# Carte_E3e_Projet_CAERUS_etudiant_ABD.net
KiCad netlist of a schematic drawn in Altium Designer
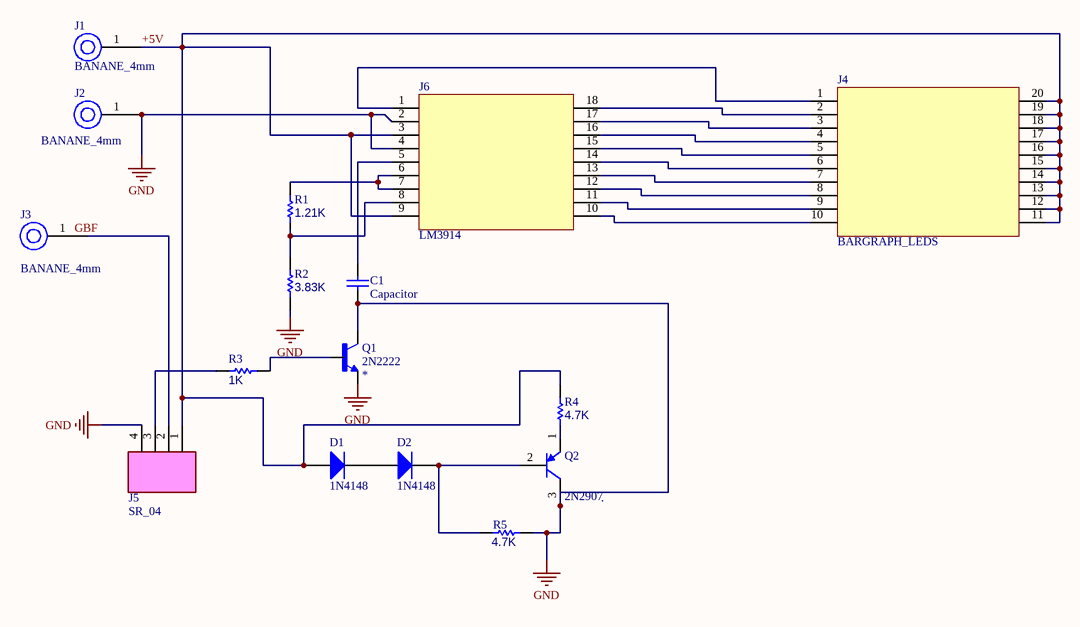
[diagram p0: Carte E3e Projet CAERUS etudiant ABD.SchDoc]

(export (version "E")
  (design (tool "Eeschema 10.0.6"))
  (components
    (comp (ref "C1")
      (value "Condensateur")
      (footprint "C0805_N")
      (description "Capacitor")
      (fields
        (field (name "TYPE") "Capacitor")
        (field (name "SOURCE") "robot_eseo.SchLib")
        (field (name "PUBLISHER") "Altium Limited")
      )
      (libsource (lib "ESEO (Ecole Supérieure d'Electronique de l'Ouest)") (part "Condensateur"))
    )
    (comp (ref "D1")
      (value "1N4148")
      (footprint "NXP-SOD27-2_V")
      (description "High Speed Diode, 100 V, 0.45 A, -65 to 175 degC, 2-Pin SOD27, RoHS, Bulk")
      (fields (field (name "POWER") "500mW") (field (name "MANUFACTURER") "Fairchild"))
      (libsource (lib "ESEO (Ecole Supérieure d'Electronique de l'Ouest)") (part "D-AK-2"))
    )
    (comp (ref "D2")
      (value "1N4148")
      (footprint "NXP-SOD27-2_V")
      (description "High Speed Diode, 100 V, 0.45 A, -65 to 175 degC, 2-Pin SOD27, RoHS, Bulk")
      (fields (field (name "POWER") "500mW") (field (name "MANUFACTURER") "Fairchild"))
      (libsource (lib "ESEO (Ecole Supérieure d'Electronique de l'Ouest)") (part "D-AK-2"))
    )
    (comp (ref "J1")
      (value "DOUILLE BANANE 4mm")
      (footprint "DOUILLE_BANANE_4mm")
      (description "DOUILLE BANANE 4 mm")
      (fields (field (name "TYPE") "BANANE_4mm"))
      (libsource (lib "connecteurs") (part "DOUILLE_BANANE_4mm"))
    )
    (comp (ref "J2")
      (value "DOUILLE BANANE 4mm")
      (footprint "DOUILLE_BANANE_4mm")
      (description "DOUILLE BANANE 4 mm")
      (fields (field (name "TYPE") "BANANE_4mm"))
      (libsource (lib "connecteurs") (part "DOUILLE_BANANE_4mm"))
    )
    (comp (ref "J3")
      (value "~")
      (footprint "DOUILLE_BANANE_4mm")
      (description "DOUILLE BANANE 4 mm")
      (fields (field (name "TYPE") "BANANE_4mm") (field (name "SOURCE") "connecteurs.SchLib"))
      (libsource (lib "ESEO (Ecole Supérieure d'Electronique de l'Ouest)") (part "DOUILLE_BANANE_4mm"))
    )
    (comp (ref "J4")
      (value "COMPOSANT_20_BROCHES")
      (footprint "DIP20_PAS=2.54_LARG=7.62_LONG=25.6")
      (fields (field (name "TYPE") "BARGRAPH_LEDS"))
      (libsource (lib "circuits integres") (part "SYMBOLE_COMPOSANT_20_BROCHES"))
    )
    (comp (ref "J5")
      (value "BARRETTE_4 CONTACTS_1 RANGEE_FEMELLE_DROITE")
      (footprint "BARRETTE_4_F_D")
      (description "BARRETTE 4 CONTACTS 1 RANGEE FEMELLE DROITE")
      (fields (field (name "TYPE") "SR_04"))
      (libsource (lib "connecteurs") (part "BARRETTE_4 CONTACTS_1 RANGEE_FEMELLE_DROITE"))
    )
    (comp (ref "J6")
      (value "COMPOSANT_18_BROCHES")
      (footprint "DIP18_PAS=2.54_LARG=7.62_LONG=23")
      (fields (field (name "TYPE") "LM3914"))
      (libsource (lib "circuits integres") (part "SYMBOLE_COMPOSANT_18_BROCHES"))
    )
    (comp (ref "Q1")
      (value "2N2222")
      (footprint "TO127P584H533-3")
      (description "Bipolar (BJT) Transistor NPN 50V 800mA 300mW Surface Mount Ceramic SMD")
      (fields (field (name "MF") "ON Semiconductor") (field (name "ALTIUM_VALUE") "*"))
      (libsource (lib "ESEO (Ecole Supérieure d'Electronique de l'Ouest)") (part "2N2222"))
    )
    (comp (ref "Q2")
      (value ".")
      (footprint "TRANSISTOR_BIPOL_TO18_EBC")
      (description "TRANSISTOR PNP TO18_EBC : 2N2907")
      (fields (field (name "TYPE") "2N2907") (field (name "SOURCE") "composants actifs.SchLib"))
      (libsource (lib "ESEO (Ecole Supérieure d'Electronique de l'Ouest)") (part "TRANSISTOR_PNP_TO92_EBC {colon} 2N5401"))
    )
    (comp (ref "R1")
      (value "1.21K")
      (footprint "RESISTANCE_1/2W")
      (description "RESISTANCE TRAVERSANTE AXIALE 1/4W")
      (fields (field (name "Comment") "RESISTANCE_AXIALE_1/4W"))
      (libsource (lib "composants passifs") (part "RESISTANCE_AXIALE_1/4W"))
    )
    (comp (ref "R2")
      (value "3.83K")
      (footprint "RESISTANCE_1/2W")
      (description "RESISTANCE TRAVERSANTE AXIALE 1/4W")
      (fields (field (name "Comment") "RESISTANCE_AXIALE_1/4W"))
      (libsource (lib "composants passifs") (part "RESISTANCE_AXIALE_1/4W"))
    )
    (comp (ref "R3")
      (value "1K")
      (footprint "RESISTANCE_1/2W")
      (description "RESISTANCE TRAVERSANTE AXIALE 1/4W")
      (fields (field (name "Comment") "RESISTANCE_AXIALE_1/4W"))
      (libsource (lib "composants passifs") (part "RESISTANCE_AXIALE_1/4W"))
    )
    (comp (ref "R4")
      (value "4.7K")
      (footprint "RESISTANCE_1W")
      (description "RESISTANCE TRAVERSANTE AXIALE 1W")
      (fields
        (field (name "Comment") "RESISTANCE_AXIALE_1W")
        (field (name "SOURCE") "composants passifs.SchLib")
      )
      (libsource (lib "ESEO (Ecole Supérieure d'Electronique de l'Ouest)") (part "RESISTANCE_AXIALE_1/4W"))
    )
    (comp (ref "R5")
      (value "4.7K")
      (footprint "RESISTANCE_1W")
      (description "RESISTANCE TRAVERSANTE AXIALE 1W")
      (fields
        (field (name "Comment") "RESISTANCE_AXIALE_1W")
        (field (name "SOURCE") "composants passifs.SchLib")
      )
      (libsource (lib "ESEO (Ecole Supérieure d'Electronique de l'Ouest)") (part "RESISTANCE_AXIALE_1/4W"))
    )
  )
  (nets
    (net (code "1") (name "/+5V") (class "Default")
      (node (ref "D1") (pin "1") (pinfunction "A_1") (pintype "passive"))
      (node (ref "J1") (pin "1") (pinfunction "1_1") (pintype "passive"))
      (node (ref "J4") (pin "11") (pintype "passive"))
      (node (ref "J4") (pin "12") (pintype "passive"))
      (node (ref "J4") (pin "13") (pintype "passive"))
      (node (ref "J4") (pin "14") (pintype "passive"))
      (node (ref "J4") (pin "15") (pintype "passive"))
      (node (ref "J4") (pin "16") (pintype "passive"))
      (node (ref "J4") (pin "17") (pintype "passive"))
      (node (ref "J4") (pin "18") (pintype "passive"))
      (node (ref "J4") (pin "19") (pintype "passive"))
      (node (ref "J4") (pin "20") (pintype "passive"))
      (node (ref "J5") (pin "1") (pinfunction "1_1") (pintype "passive"))
      (node (ref "J6") (pin "3") (pintype "passive"))
      (node (ref "J6") (pin "9") (pintype "passive"))
      (node (ref "R4") (pin "2") (pinfunction "2_2") (pintype "passive"))
    )
    (net (code "2") (name "GND") (class "Default")
      (node (ref "C1") (pin "1") (pinfunction "1_1") (pintype "passive"))
      (node (ref "J2") (pin "1") (pinfunction "1_1") (pintype "passive"))
      (node (ref "J5") (pin "4") (pinfunction "4_4") (pintype "passive"))
      (node (ref "J6") (pin "2") (pintype "passive"))
      (node (ref "J6") (pin "4") (pintype "passive"))
      (node (ref "Q1") (pin "1") (pinfunction "E_1") (pintype "passive"))
      (node (ref "Q1") (pin "3") (pinfunction "C_3") (pintype "passive"))
      (node (ref "Q2") (pin "3") (pinfunction "C_3") (pintype "passive"))
      (node (ref "R2") (pin "1") (pinfunction "1_1") (pintype "passive"))
      (node (ref "R5") (pin "2") (pinfunction "2_2") (pintype "passive"))
    )
    (net (code "3") (name "Net-(C1-Pad2)") (class "Default")
      (node (ref "C1") (pin "2") (pinfunction "2_2") (pintype "passive"))
      (node (ref "J6") (pin "5") (pintype "passive"))
    )
    (net (code "4") (name "Net-(D1-K)") (class "Default")
      (node (ref "D1") (pin "2") (pinfunction "K_2") (pintype "passive"))
      (node (ref "D2") (pin "1") (pinfunction "A_1") (pintype "passive"))
    )
    (net (code "5") (name "Net-(D2-K)") (class "Default")
      (node (ref "D2") (pin "2") (pinfunction "K_2") (pintype "passive"))
      (node (ref "Q2") (pin "2") (pinfunction "B_2") (pintype "passive"))
      (node (ref "R5") (pin "1") (pinfunction "1_1") (pintype "passive"))
    )
    (net (code "6") (name "Net-(J3-Pad1)") (class "Default")
      (node (ref "J3") (pin "1") (pinfunction "1_1") (pintype "passive"))
      (node (ref "J5") (pin "2") (pinfunction "2_2") (pintype "passive"))
    )
    (net (code "7") (name "Net-(J4-Pad1)") (class "Default")
      (node (ref "J4") (pin "1") (pintype "passive"))
      (node (ref "J6") (pin "1") (pintype "passive"))
    )
    (net (code "8") (name "Net-(J4-Pad2)") (class "Default")
      (node (ref "J4") (pin "2") (pintype "passive"))
      (node (ref "J6") (pin "18") (pintype "passive"))
    )
    (net (code "9") (name "Net-(J4-Pad3)") (class "Default")
      (node (ref "J4") (pin "3") (pintype "passive"))
      (node (ref "J6") (pin "17") (pintype "passive"))
    )
    (net (code "10") (name "Net-(J4-Pad4)") (class "Default")
      (node (ref "J4") (pin "4") (pintype "passive"))
      (node (ref "J6") (pin "16") (pintype "passive"))
    )
    (net (code "11") (name "Net-(J4-Pad5)") (class "Default")
      (node (ref "J4") (pin "5") (pintype "passive"))
      (node (ref "J6") (pin "15") (pintype "passive"))
    )
    (net (code "12") (name "Net-(J4-Pad6)") (class "Default")
      (node (ref "J4") (pin "6") (pintype "passive"))
      (node (ref "J6") (pin "14") (pintype "passive"))
    )
    (net (code "13") (name "Net-(J4-Pad7)") (class "Default")
      (node (ref "J4") (pin "7") (pintype "passive"))
      (node (ref "J6") (pin "13") (pintype "passive"))
    )
    (net (code "14") (name "Net-(J4-Pad8)") (class "Default")
      (node (ref "J4") (pin "8") (pintype "passive"))
      (node (ref "J6") (pin "12") (pintype "passive"))
    )
    (net (code "15") (name "Net-(J4-Pad9)") (class "Default")
      (node (ref "J4") (pin "9") (pintype "passive"))
      (node (ref "J6") (pin "11") (pintype "passive"))
    )
    (net (code "16") (name "Net-(J4-Pad10)") (class "Default")
      (node (ref "J4") (pin "10") (pintype "passive"))
      (node (ref "J6") (pin "10") (pintype "passive"))
    )
    (net (code "17") (name "Net-(J5-Pad3)") (class "Default")
      (node (ref "J5") (pin "3") (pinfunction "3_3") (pintype "passive"))
      (node (ref "R3") (pin "1") (pinfunction "1_1") (pintype "passive"))
    )
    (net (code "18") (name "Net-(J6-Pad6)") (class "Default")
      (node (ref "J6") (pin "6") (pintype "passive"))
      (node (ref "J6") (pin "7") (pintype "passive"))
      (node (ref "R1") (pin "2") (pinfunction "2_2") (pintype "passive"))
    )
    (net (code "19") (name "Net-(J6-Pad8)") (class "Default")
      (node (ref "J6") (pin "8") (pintype "passive"))
      (node (ref "R1") (pin "1") (pinfunction "1_1") (pintype "passive"))
      (node (ref "R2") (pin "2") (pinfunction "2_2") (pintype "passive"))
    )
    (net (code "20") (name "Net-(Q1-B)") (class "Default")
      (node (ref "Q1") (pin "2") (pinfunction "B_2") (pintype "passive"))
      (node (ref "R3") (pin "2") (pinfunction "2_2") (pintype "passive"))
    )
    (net (code "21") (name "Net-(Q2-E)") (class "Default")
      (node (ref "Q2") (pin "1") (pinfunction "E_1") (pintype "passive"))
      (node (ref "R4") (pin "1") (pinfunction "1_1") (pintype "passive"))
    )
  )
)
